# Puzzle_Magnetic_switch.net
KiCad netlist of a schematic drawn in EAGLE
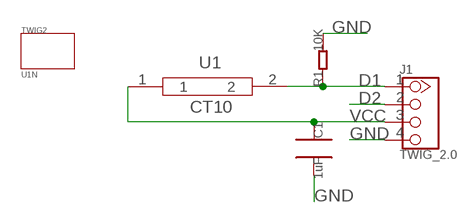
[diagram p0: schematic, sheet 1]

(export (version "E")
  (design (tool "Eeschema 10.0.6"))
  (components
    (comp (ref "C1")
      (value "1uF")
      (footprint "eagle-import:0805")
      (libsource (lib "eagle-import") (part "C0805"))
    )
    (comp (ref "J1")
      (value "TWIG_2.0")
      (footprint "eagle-import:2.0_1X4")
      (libsource (lib "eagle-import") (part "TWIG_2.0"))
    )
    (comp (ref "R1")
      (value "10K")
      (footprint "eagle-import:0805")
      (libsource (lib "eagle-import") (part "R0805"))
    )
    (comp (ref "TWIG2")
      (value "U1N")
      (footprint "eagle-import:U1N")
      (libsource (lib "eagle-import") (part "U1N"))
    )
    (comp (ref "U1")
      (value "MAGNETISM")
      (footprint "eagle-import:MAGNETISM")
      (libsource (lib "eagle-import") (part "MAGNETISM"))
    )
  )
  (nets
    (net (code "1") (name "/D1") (class "Default")
      (node (ref "J1") (pin "1") (pinfunction "1_1") (pintype "bidirectional"))
      (node (ref "R1") (pin "1") (pinfunction "1_1") (pintype "bidirectional"))
      (node (ref "U1") (pin "2") (pinfunction "2_2") (pintype "bidirectional"))
    )
    (net (code "2") (name "/D2") (class "Default")
      (node (ref "J1") (pin "2") (pinfunction "2_2") (pintype "bidirectional"))
    )
    (net (code "3") (name "/GND") (class "Default")
      (node (ref "C1") (pin "2") (pinfunction "2_2") (pintype "bidirectional"))
      (node (ref "J1") (pin "4") (pinfunction "4_4") (pintype "bidirectional"))
      (node (ref "R1") (pin "2") (pinfunction "2_2") (pintype "bidirectional"))
    )
    (net (code "4") (name "/VCC") (class "Default")
      (node (ref "C1") (pin "1") (pinfunction "1_1") (pintype "bidirectional"))
      (node (ref "J1") (pin "3") (pinfunction "3_3") (pintype "bidirectional"))
      (node (ref "U1") (pin "1") (pinfunction "1_1") (pintype "bidirectional"))
    )
  )
)
